# 13-_EtherCAT.net
KiCad netlist of a schematic drawn in Altium Designer
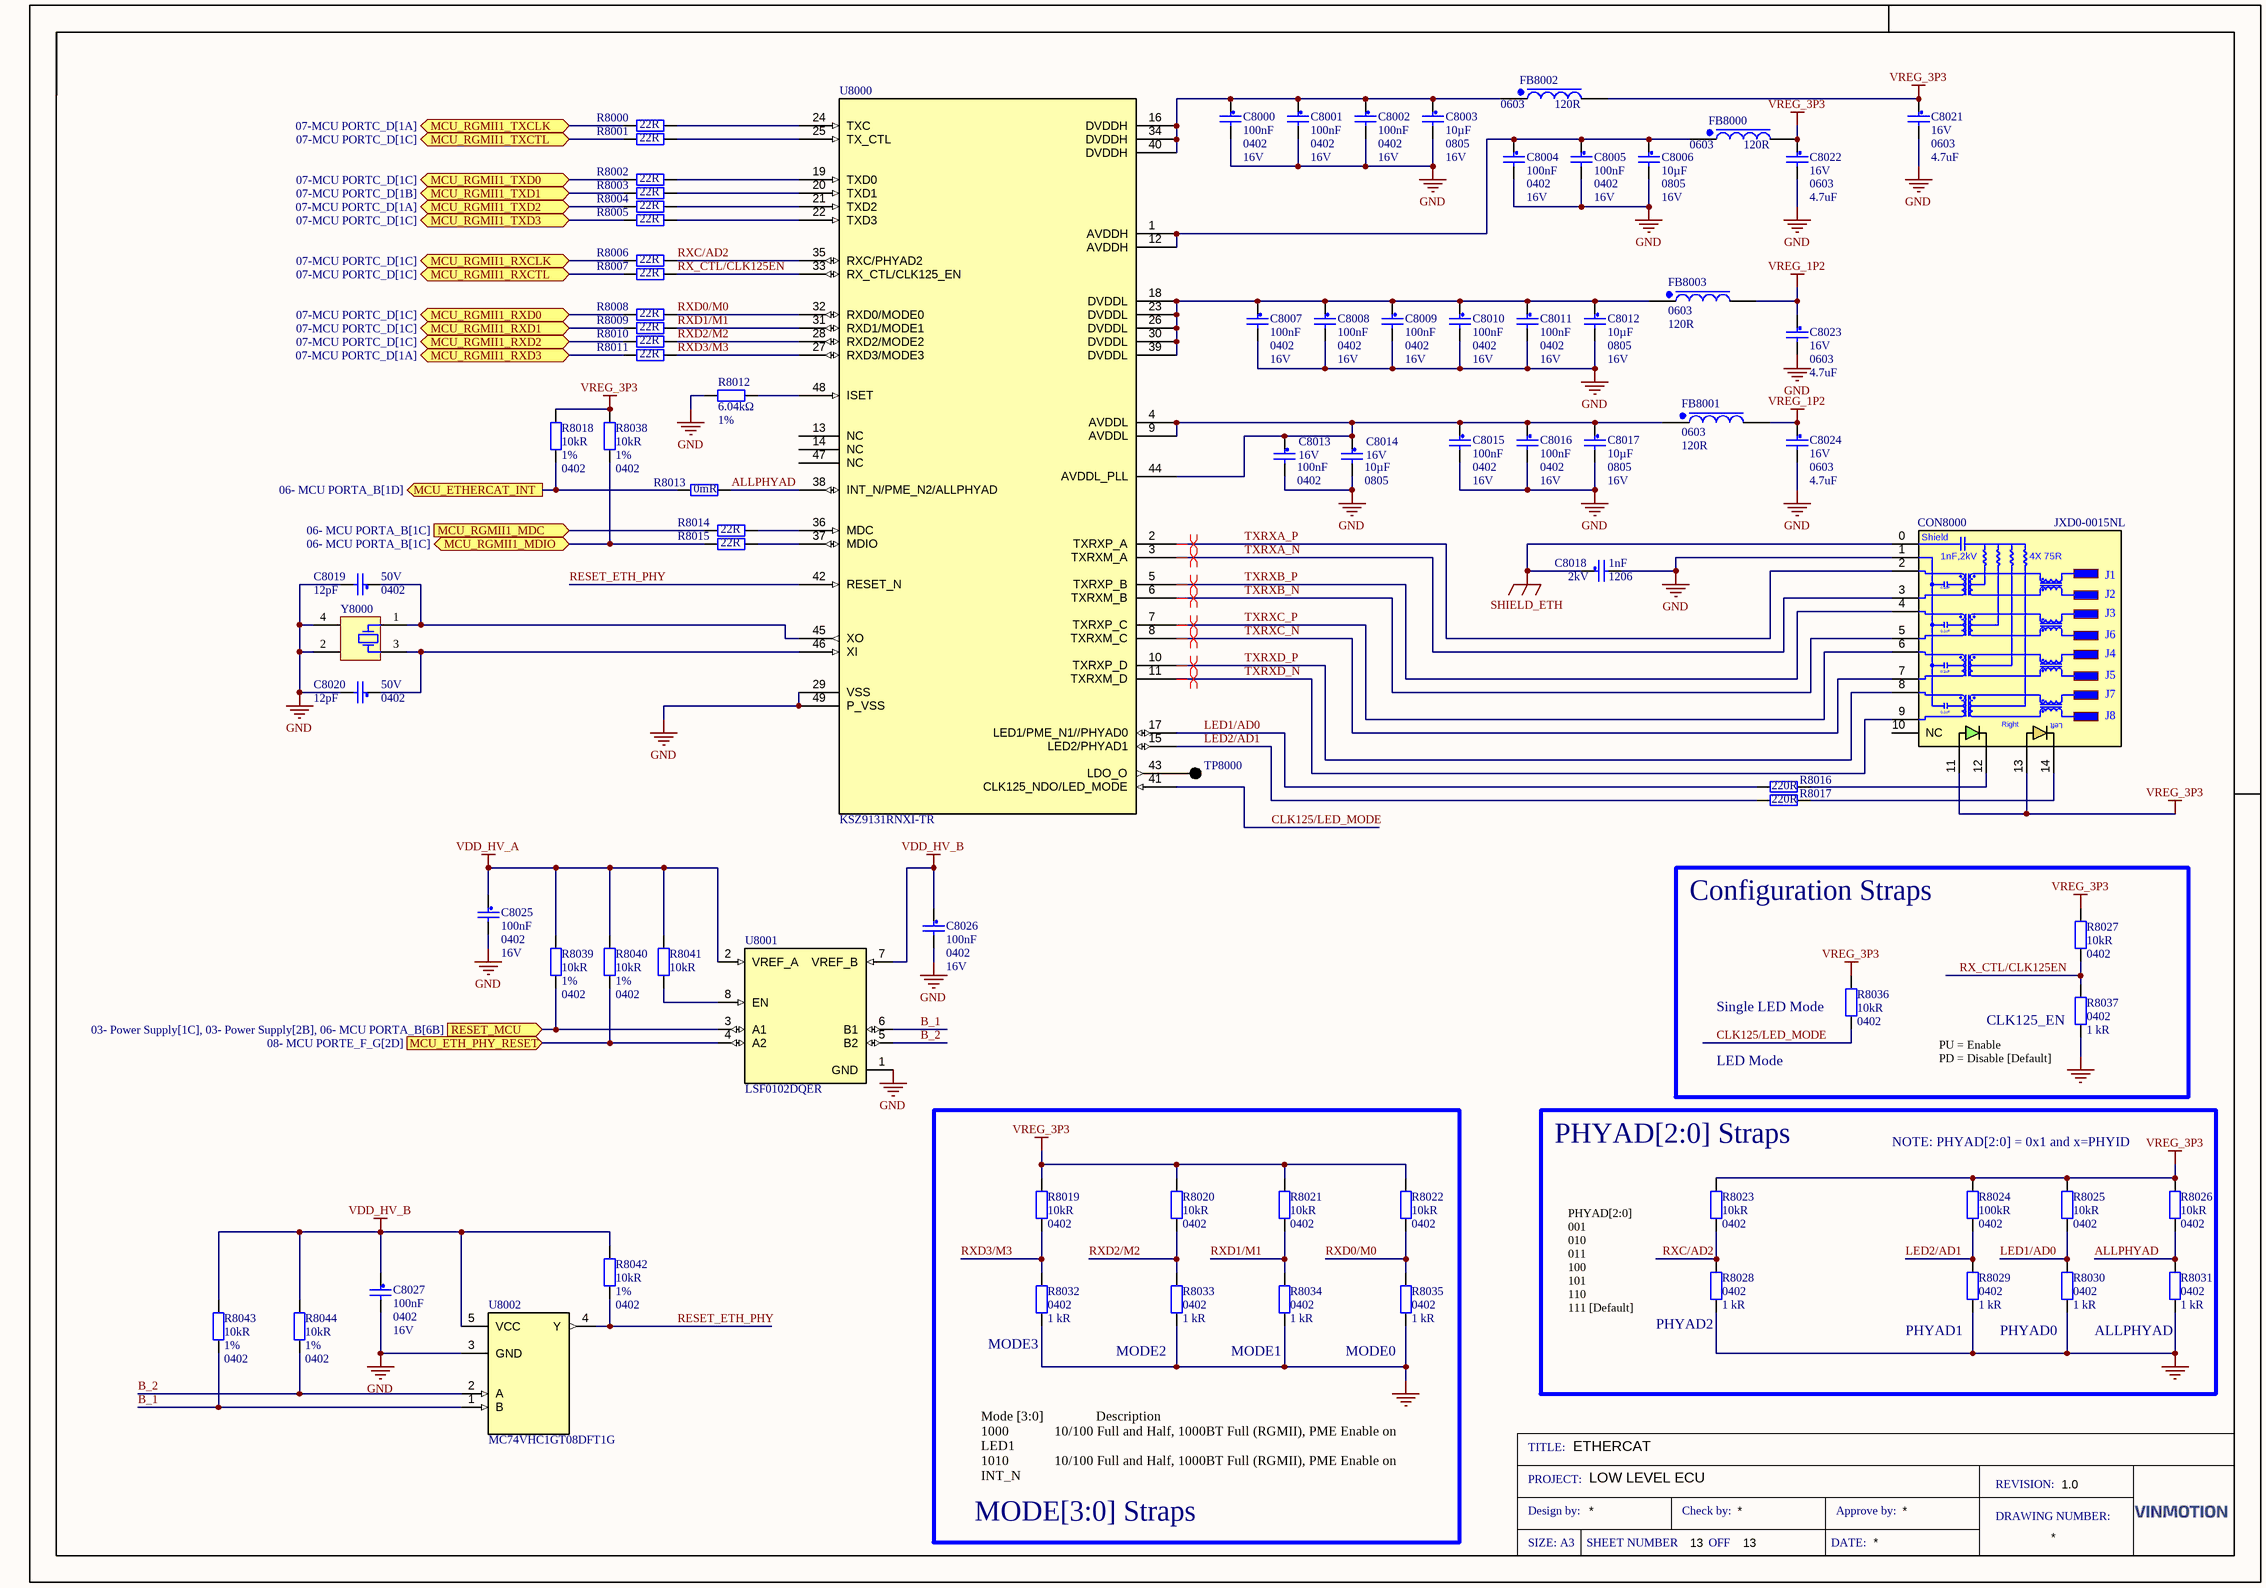
[diagram p0: 13- EtherCAT.SchDoc]

(export (version "E")
  (design (tool "Eeschema 10.0.6"))
  (components
    (comp (ref "C8000")
      (value "0402YC104KAT2A")
      (footprint "CAP0402")
      (description "CAP CER 0.1UF 16V X7R 0402")
      (fields
        (field (name "CAPACITANCE") "100nF")
        (field (name "CASE/PACKAGE") "0402")
        (field (name "VOLTAGE RATING (DC)") "16V")
      )
      (libsource (lib "VMO_Lib") (part "CMP-00988-1"))
    )
    (comp (ref "C8001")
      (value "0402YC104KAT2A")
      (footprint "CAP0402")
      (description "CAP CER 0.1UF 16V X7R 0402")
      (fields
        (field (name "CAPACITANCE") "100nF")
        (field (name "CASE/PACKAGE") "0402")
        (field (name "VOLTAGE RATING (DC)") "16V")
      )
      (libsource (lib "VMO_Lib") (part "CMP-00988-1"))
    )
    (comp (ref "C8002")
      (value "0402YC104KAT2A")
      (footprint "CAP0402")
      (description "CAP CER 0.1UF 16V X7R 0402")
      (fields
        (field (name "CAPACITANCE") "100nF")
        (field (name "CASE/PACKAGE") "0402")
        (field (name "VOLTAGE RATING (DC)") "16V")
      )
      (libsource (lib "VMO_Lib") (part "CMP-00988-1"))
    )
    (comp (ref "C8003")
      (value "10µF")
      (footprint "CAP0805")
      (description "CAP CER 10UF 16V X7R 0805")
      (fields
        (field (name "CASE/PACKAGE") "0805")
        (field (name "MANUFACTURER") "Murata")
        (field (name "MANUFACTURER PART NUMBER") "GRM21BZ71C106KE15L")
        (field (name "VOLTAGE RATING") "16V")
      )
      (libsource (lib "VMO_Lib") (part "CMP-01170-1"))
    )
    (comp (ref "C8004")
      (value "0402YC104KAT2A")
      (footprint "CAP0402")
      (description "CAP CER 0.1UF 16V X7R 0402")
      (fields
        (field (name "CAPACITANCE") "100nF")
        (field (name "CASE/PACKAGE") "0402")
        (field (name "VOLTAGE RATING (DC)") "16V")
      )
      (libsource (lib "VMO_Lib") (part "CMP-00988-1"))
    )
    (comp (ref "C8005")
      (value "0402YC104KAT2A")
      (footprint "CAP0402")
      (description "CAP CER 0.1UF 16V X7R 0402")
      (fields
        (field (name "CAPACITANCE") "100nF")
        (field (name "CASE/PACKAGE") "0402")
        (field (name "VOLTAGE RATING (DC)") "16V")
      )
      (libsource (lib "VMO_Lib") (part "CMP-00988-1"))
    )
    (comp (ref "C8006")
      (value "10µF")
      (footprint "CAP0805")
      (description "CAP CER 10UF 16V X7R 0805")
      (fields
        (field (name "CASE/PACKAGE") "0805")
        (field (name "MANUFACTURER") "Murata")
        (field (name "MANUFACTURER PART NUMBER") "GRM21BZ71C106KE15L")
        (field (name "VOLTAGE RATING") "16V")
      )
      (libsource (lib "VMO_Lib") (part "CMP-01170-1"))
    )
    (comp (ref "C8007")
      (value "0402YC104KAT2A")
      (footprint "CAP0402")
      (description "CAP CER 0.1UF 16V X7R 0402")
      (fields
        (field (name "CAPACITANCE") "100nF")
        (field (name "CASE/PACKAGE") "0402")
        (field (name "VOLTAGE RATING (DC)") "16V")
      )
      (libsource (lib "VMO_Lib") (part "CMP-00988-1"))
    )
    (comp (ref "C8008")
      (value "0402YC104KAT2A")
      (footprint "CAP0402")
      (description "CAP CER 0.1UF 16V X7R 0402")
      (fields
        (field (name "CAPACITANCE") "100nF")
        (field (name "CASE/PACKAGE") "0402")
        (field (name "VOLTAGE RATING (DC)") "16V")
      )
      (libsource (lib "VMO_Lib") (part "CMP-00988-1"))
    )
    (comp (ref "C8009")
      (value "0402YC104KAT2A")
      (footprint "CAP0402")
      (description "CAP CER 0.1UF 16V X7R 0402")
      (fields
        (field (name "CAPACITANCE") "100nF")
        (field (name "CASE/PACKAGE") "0402")
        (field (name "VOLTAGE RATING (DC)") "16V")
      )
      (libsource (lib "VMO_Lib") (part "CMP-00988-1"))
    )
    (comp (ref "C8010")
      (value "0402YC104KAT2A")
      (footprint "CAP0402")
      (description "CAP CER 0.1UF 16V X7R 0402")
      (fields
        (field (name "CAPACITANCE") "100nF")
        (field (name "CASE/PACKAGE") "0402")
        (field (name "VOLTAGE RATING (DC)") "16V")
      )
      (libsource (lib "VMO_Lib") (part "CMP-00988-1"))
    )
    (comp (ref "C8011")
      (value "0402YC104KAT2A")
      (footprint "CAP0402")
      (description "CAP CER 0.1UF 16V X7R 0402")
      (fields
        (field (name "CAPACITANCE") "100nF")
        (field (name "CASE/PACKAGE") "0402")
        (field (name "VOLTAGE RATING (DC)") "16V")
      )
      (libsource (lib "VMO_Lib") (part "CMP-00988-1"))
    )
    (comp (ref "C8012")
      (value "10µF")
      (footprint "CAP0805")
      (description "CAP CER 10UF 16V X7R 0805")
      (fields
        (field (name "CASE/PACKAGE") "0805")
        (field (name "MANUFACTURER") "Murata")
        (field (name "MANUFACTURER PART NUMBER") "GRM21BZ71C106KE15L")
        (field (name "VOLTAGE RATING") "16V")
      )
      (libsource (lib "VMO_Lib") (part "CMP-01170-1"))
    )
    (comp (ref "C8013")
      (value "0402YC104KAT2A")
      (footprint "CAP0402")
      (description "CAP CER 0.1UF 16V X7R 0402")
      (fields
        (field (name "CAPACITANCE") "100nF")
        (field (name "CASE/PACKAGE") "0402")
        (field (name "VOLTAGE RATING (DC)") "16V")
      )
      (libsource (lib "VMO_Lib") (part "CMP-00988-1"))
    )
    (comp (ref "C8014")
      (value "10µF")
      (footprint "CAP0805")
      (description "CAP CER 10UF 16V X7R 0805")
      (fields
        (field (name "CASE/PACKAGE") "0805")
        (field (name "MANUFACTURER") "Murata")
        (field (name "MANUFACTURER PART NUMBER") "GRM21BZ71C106KE15L")
        (field (name "VOLTAGE RATING") "16V")
      )
      (libsource (lib "VMO_Lib") (part "CMP-01170-1"))
    )
    (comp (ref "C8015")
      (value "0402YC104KAT2A")
      (footprint "CAP0402")
      (description "CAP CER 0.1UF 16V X7R 0402")
      (fields
        (field (name "CAPACITANCE") "100nF")
        (field (name "CASE/PACKAGE") "0402")
        (field (name "VOLTAGE RATING (DC)") "16V")
      )
      (libsource (lib "VMO_Lib") (part "CMP-00988-1"))
    )
    (comp (ref "C8016")
      (value "0402YC104KAT2A")
      (footprint "CAP0402")
      (description "CAP CER 0.1UF 16V X7R 0402")
      (fields
        (field (name "CAPACITANCE") "100nF")
        (field (name "CASE/PACKAGE") "0402")
        (field (name "VOLTAGE RATING (DC)") "16V")
      )
      (libsource (lib "VMO_Lib") (part "CMP-00988-1"))
    )
    (comp (ref "C8017")
      (value "10µF")
      (footprint "CAP0805")
      (description "CAP CER 10UF 16V X7R 0805")
      (fields
        (field (name "CASE/PACKAGE") "0805")
        (field (name "MANUFACTURER") "Murata")
        (field (name "MANUFACTURER PART NUMBER") "GRM21BZ71C106KE15L")
        (field (name "VOLTAGE RATING") "16V")
      )
      (libsource (lib "VMO_Lib") (part "CMP-01170-1"))
    )
    (comp (ref "C8018")
      (value "C1206C102KGRACAUTO")
      (footprint "CAP1206")
      (description "CAP CER 1000PF 2KV X7R 1206")
      (fields
        (field (name "TOLERANCE") "10%")
        (field (name "VOLTAGE RATING") "2kV")
        (field (name "CASE/PACKAGE") "1206")
        (field (name "CAPACITANCE") "1nF")
      )
      (libsource (lib "VMO_Lib") (part "CMP-00118-3"))
    )
    (comp (ref "C8019")
      (value "GCM1555C1H120JA16D")
      (footprint "CAP0402")
      (description "CAP CER 12PF 50V C0G/NP0 0402")
      (fields
        (field (name "TOLERANCE") "5%")
        (field (name "VOLTAGE RATING") "50V")
        (field (name "CASE/PACKAGE") "0402")
        (field (name "CAPACITANCE") "12pF")
      )
      (libsource (lib "VMO_Lib") (part "CMP-00203-1"))
    )
    (comp (ref "C8020")
      (value "GCM1555C1H120JA16D")
      (footprint "CAP0402")
      (description "CAP CER 12PF 50V C0G/NP0 0402")
      (fields
        (field (name "TOLERANCE") "5%")
        (field (name "VOLTAGE RATING") "50V")
        (field (name "CASE/PACKAGE") "0402")
        (field (name "CAPACITANCE") "12pF")
      )
      (libsource (lib "VMO_Lib") (part "CMP-00203-1"))
    )
    (comp (ref "C8021")
      (value "GRT188C81C475KE13D")
      (footprint "CAP0603")
      (description "CAP CER 4.7uF 16V 10% X6S 0603 SMD")
      (fields
        (field (name "TOLERANCE") "10%")
        (field (name "VOLTAGE RATING") "16V")
        (field (name "CASE/PACKAGE") "0603")
        (field (name "CAPACITANCE") "4.7uF")
      )
      (libsource (lib "VMO_Lib") (part "CMP-00351-2"))
    )
    (comp (ref "C8022")
      (value "GRT188C81C475KE13D")
      (footprint "CAP0603")
      (description "CAP CER 4.7uF 16V 10% X6S 0603 SMD")
      (fields
        (field (name "TOLERANCE") "10%")
        (field (name "VOLTAGE RATING") "16V")
        (field (name "CASE/PACKAGE") "0603")
        (field (name "CAPACITANCE") "4.7uF")
      )
      (libsource (lib "VMO_Lib") (part "CMP-00351-2"))
    )
    (comp (ref "C8023")
      (value "GRT188C81C475KE13D")
      (footprint "CAP0603")
      (description "CAP CER 4.7uF 16V 10% X6S 0603 SMD")
      (fields
        (field (name "TOLERANCE") "10%")
        (field (name "VOLTAGE RATING") "16V")
        (field (name "CASE/PACKAGE") "0603")
        (field (name "CAPACITANCE") "4.7uF")
      )
      (libsource (lib "VMO_Lib") (part "CMP-00351-2"))
    )
    (comp (ref "C8024")
      (value "GRT188C81C475KE13D")
      (footprint "CAP0603")
      (description "CAP CER 4.7uF 16V 10% X6S 0603 SMD")
      (fields
        (field (name "TOLERANCE") "10%")
        (field (name "VOLTAGE RATING") "16V")
        (field (name "CASE/PACKAGE") "0603")
        (field (name "CAPACITANCE") "4.7uF")
      )
      (libsource (lib "VMO_Lib") (part "CMP-00351-2"))
    )
    (comp (ref "C8025")
      (value "0402YC104KAT2A")
      (footprint "CAP0402")
      (description "CAP CER 0.1UF 16V X7R 0402")
      (fields
        (field (name "CAPACITANCE") "100nF")
        (field (name "CASE/PACKAGE") "0402")
        (field (name "VOLTAGE RATING (DC)") "16V")
      )
      (libsource (lib "VMO_Lib") (part "CMP-00988-1"))
    )
    (comp (ref "C8026")
      (value "0402YC104KAT2A")
      (footprint "CAP0402")
      (description "CAP CER 0.1UF 16V X7R 0402")
      (fields
        (field (name "CAPACITANCE") "100nF")
        (field (name "CASE/PACKAGE") "0402")
        (field (name "VOLTAGE RATING (DC)") "16V")
      )
      (libsource (lib "VMO_Lib") (part "CMP-00988-1"))
    )
    (comp (ref "C8027")
      (value "0402YC104KAT2A")
      (footprint "CAP0402")
      (description "CAP CER 0.1UF 16V X7R 0402")
      (fields
        (field (name "CAPACITANCE") "100nF")
        (field (name "CASE/PACKAGE") "0402")
        (field (name "VOLTAGE RATING (DC)") "16V")
      )
      (libsource (lib "VMO_Lib") (part "CMP-00988-1"))
    )
    (comp (ref "CON8000")
      (value "JXD0-0015NL")
      (footprint "RJ45")
      (description "1 Port RJ45 Through Hole 10/100/1000 Base-T, AutoMDIX")
      (fields (field (name "MANUFACTURER") "Pulse Electronics"))
      (libsource (lib "VMO_Lib") (part "CMP-01191-1"))
    )
    (comp (ref "FB8000")
      (value "BLM18KG121TH1D")
      (footprint "FB0603")
      (description "FERRITE BEAD 120 OHM 0603 1LN")
      (fields (field (name "CASE/PACKAGE") "0603") (field (name "IMPEDANCE") "120R"))
      (libsource (lib "VMO_Lib") (part "CMP-ROOT-0013-6"))
    )
    (comp (ref "FB8001")
      (value "BLM18KG121TH1D")
      (footprint "FB0603")
      (description "FERRITE BEAD 120 OHM 0603 1LN")
      (fields (field (name "CASE/PACKAGE") "0603") (field (name "IMPEDANCE") "120R"))
      (libsource (lib "VMO_Lib") (part "CMP-ROOT-0013-6"))
    )
    (comp (ref "FB8002")
      (value "BLM18KG121TH1D")
      (footprint "FB0603")
      (description "FERRITE BEAD 120 OHM 0603 1LN")
      (fields (field (name "CASE/PACKAGE") "0603") (field (name "IMPEDANCE") "120R"))
      (libsource (lib "VMO_Lib") (part "CMP-ROOT-0013-6"))
    )
    (comp (ref "FB8003")
      (value "BLM18KG121TH1D")
      (footprint "FB0603")
      (description "FERRITE BEAD 120 OHM 0603 1LN")
      (fields (field (name "CASE/PACKAGE") "0603") (field (name "IMPEDANCE") "120R"))
      (libsource (lib "VMO_Lib") (part "CMP-ROOT-0013-6"))
    )
    (comp (ref "R8000")
      (value "CRCW040222R0JNED")
      (footprint "RES0402")
      (description "RES SMD 22 OHM 5% 1/16W 0402")
      (fields (field (name "TOLERANCE") "5%") (field (name "RESISTANCE") "22R"))
      (libsource (lib "VMO_Lib") (part "CMP-00237-1"))
    )
    (comp (ref "R8001")
      (value "CRCW040222R0JNED")
      (footprint "RES0402")
      (description "RES SMD 22 OHM 5% 1/16W 0402")
      (fields (field (name "TOLERANCE") "5%") (field (name "RESISTANCE") "22R"))
      (libsource (lib "VMO_Lib") (part "CMP-00237-1"))
    )
    (comp (ref "R8002")
      (value "CRCW040222R0JNED")
      (footprint "RES0402")
      (description "RES SMD 22 OHM 5% 1/16W 0402")
      (fields (field (name "TOLERANCE") "5%") (field (name "RESISTANCE") "22R"))
      (libsource (lib "VMO_Lib") (part "CMP-00237-1"))
    )
    (comp (ref "R8003")
      (value "CRCW040222R0JNED")
      (footprint "RES0402")
      (description "RES SMD 22 OHM 5% 1/16W 0402")
      (fields (field (name "TOLERANCE") "5%") (field (name "RESISTANCE") "22R"))
      (libsource (lib "VMO_Lib") (part "CMP-00237-1"))
    )
    (comp (ref "R8004")
      (value "CRCW040222R0JNED")
      (footprint "RES0402")
      (description "RES SMD 22 OHM 5% 1/16W 0402")
      (fields (field (name "TOLERANCE") "5%") (field (name "RESISTANCE") "22R"))
      (libsource (lib "VMO_Lib") (part "CMP-00237-1"))
    )
    (comp (ref "R8005")
      (value "CRCW040222R0JNED")
      (footprint "RES0402")
      (description "RES SMD 22 OHM 5% 1/16W 0402")
      (fields (field (name "TOLERANCE") "5%") (field (name "RESISTANCE") "22R"))
      (libsource (lib "VMO_Lib") (part "CMP-00237-1"))
    )
    (comp (ref "R8006")
      (value "CRCW040222R0JNED")
      (footprint "RES0402")
      (description "RES SMD 22 OHM 5% 1/16W 0402")
      (fields (field (name "TOLERANCE") "5%") (field (name "RESISTANCE") "22R"))
      (libsource (lib "VMO_Lib") (part "CMP-00237-1"))
    )
    (comp (ref "R8007")
      (value "CRCW040222R0JNED")
      (footprint "RES0402")
      (description "RES SMD 22 OHM 5% 1/16W 0402")
      (fields (field (name "TOLERANCE") "5%") (field (name "RESISTANCE") "22R"))
      (libsource (lib "VMO_Lib") (part "CMP-00237-1"))
    )
    (comp (ref "R8008")
      (value "CRCW040222R0JNED")
      (footprint "RES0402")
      (description "RES SMD 22 OHM 5% 1/16W 0402")
      (fields (field (name "TOLERANCE") "5%") (field (name "RESISTANCE") "22R"))
      (libsource (lib "VMO_Lib") (part "CMP-00237-1"))
    )
    (comp (ref "R8009")
      (value "CRCW040222R0JNED")
      (footprint "RES0402")
      (description "RES SMD 22 OHM 5% 1/16W 0402")
      (fields (field (name "TOLERANCE") "5%") (field (name "RESISTANCE") "22R"))
      (libsource (lib "VMO_Lib") (part "CMP-00237-1"))
    )
    (comp (ref "R8010")
      (value "CRCW040222R0JNED")
      (footprint "RES0402")
      (description "RES SMD 22 OHM 5% 1/16W 0402")
      (fields (field (name "TOLERANCE") "5%") (field (name "RESISTANCE") "22R"))
      (libsource (lib "VMO_Lib") (part "CMP-00237-1"))
    )
    (comp (ref "R8011")
      (value "CRCW040222R0JNED")
      (footprint "RES0402")
      (description "RES SMD 22 OHM 5% 1/16W 0402")
      (fields (field (name "TOLERANCE") "5%") (field (name "RESISTANCE") "22R"))
      (libsource (lib "VMO_Lib") (part "CMP-00237-1"))
    )
    (comp (ref "R8012")
      (value "6.04kΩ")
      (footprint "RES0402")
      (description "RES 6.04K OHM 1% 1/16W 0402")
      (fields
        (field (name "MANUFACTURER") "Vishay")
        (field (name "MANUFACTURER PART NUMBER") "CRCW04026K04FKEDC")
        (field (name "TOLERANCE") "1%")
      )
      (libsource (lib "VMO_Lib") (part "CMP-01177-1"))
    )
    (comp (ref "R8013")
      (value "RMCF0402ZT0R00")
      (footprint "RES0402")
      (description "RES 0R 1/16W 1% 0402 SMD")
      (fields (field (name "RESISTANCE") "0mR"))
      (libsource (lib "VMO_Lib") (part "CMP-ROOT-0037-10"))
    )
    (comp (ref "R8014")
      (value "CRCW040222R0JNED")
      (footprint "RES0402")
      (description "RES SMD 22 OHM 5% 1/16W 0402")
      (fields (field (name "TOLERANCE") "5%") (field (name "RESISTANCE") "22R"))
      (libsource (lib "VMO_Lib") (part "CMP-00237-1"))
    )
    (comp (ref "R8015")
      (value "CRCW040222R0JNED")
      (footprint "RES0402")
      (description "RES SMD 22 OHM 5% 1/16W 0402")
      (fields (field (name "TOLERANCE") "5%") (field (name "RESISTANCE") "22R"))
      (libsource (lib "VMO_Lib") (part "CMP-00237-1"))
    )
    (comp (ref "R8016")
      (value "220R")
      (footprint "RES0402")
      (description "RES SMD 220 OHM 1% 1/10W 0402")
      (fields
        (field (name "MANUFACTURER") "Vishay")
        (field (name "MANUFACTURER PART NUMBER") "CRCW0402220RFKED")
      )
      (libsource (lib "VMO_Lib") (part "CMP-01126-1"))
    )
    (comp (ref "R8017")
      (value "220R")
      (footprint "RES0402")
      (description "RES SMD 220 OHM 1% 1/10W 0402")
      (fields
        (field (name "MANUFACTURER") "Vishay")
        (field (name "MANUFACTURER PART NUMBER") "CRCW0402220RFKED")
      )
      (libsource (lib "VMO_Lib") (part "CMP-01126-1"))
    )
    (comp (ref "R8018")
      (value "10kR")
      (footprint "RES0402")
      (description "RES 10K OHM 1% 1/16W 0402")
      (fields
        (field (name "MANUFACTURER") "Stackpole Electronics")
        (field (name "MANUFACTURER PART NUMBER") "RMCF0402FT10K0")
        (field (name "TOLERANCE") "1%")
        (field (name "CASE/PACKAGE") "0402")
      )
      (libsource (lib "VMO_Lib") (part "CMP-01105-1"))
    )
    (comp (ref "R8019")
      (value "ERJ2GEJ103X")
      (footprint "RES0402")
      (description "RES SMD 10K OHM 5% 1/10W 0402")
      (fields
        (field (name "TOLERANCE") "5%")
        (field (name "RESISTANCE") "10kR")
        (field (name "CASE/PACKAGE") "0402")
      )
      (libsource (lib "VMO_Lib") (part "CMP-00039-6"))
    )
    (comp (ref "R8020")
      (value "ERJ2GEJ103X")
      (footprint "RES0402")
      (description "RES SMD 10K OHM 5% 1/10W 0402")
      (fields
        (field (name "TOLERANCE") "5%")
        (field (name "RESISTANCE") "10kR")
        (field (name "CASE/PACKAGE") "0402")
      )
      (libsource (lib "VMO_Lib") (part "CMP-00039-6"))
    )
    (comp (ref "R8021")
      (value "ERJ2GEJ103X")
      (footprint "RES0402")
      (description "RES SMD 10K OHM 5% 1/10W 0402")
      (fields
        (field (name "TOLERANCE") "5%")
        (field (name "RESISTANCE") "10kR")
        (field (name "CASE/PACKAGE") "0402")
      )
      (libsource (lib "VMO_Lib") (part "CMP-00039-6"))
    )
    (comp (ref "R8022")
      (value "ERJ2GEJ103X")
      (footprint "RES0402")
      (description "RES SMD 10K OHM 5% 1/10W 0402")
      (fields
        (field (name "TOLERANCE") "5%")
        (field (name "RESISTANCE") "10kR")
        (field (name "CASE/PACKAGE") "0402")
      )
      (libsource (lib "VMO_Lib") (part "CMP-00039-6"))
    )
    (comp (ref "R8023")
      (value "ERJ2GEJ103X")
      (footprint "RES0402")
      (description "RES SMD 10K OHM 5% 1/10W 0402")
      (fields
        (field (name "TOLERANCE") "5%")
        (field (name "RESISTANCE") "10kR")
        (field (name "CASE/PACKAGE") "0402")
      )
      (libsource (lib "VMO_Lib") (part "CMP-00039-6"))
    )
    (comp (ref "R8024")
      (value "RMCF0402FT100K")
      (footprint "RES0402")
      (description "RES 100kR 1/16W 1% 0402 SMD")
      (fields
        (field (name "TOLERANCE") "1%")
        (field (name "RESISTANCE") "100kR")
        (field (name "CASE/PACKAGE") "0402")
      )
      (libsource (lib "VMO_Lib") (part "CMP-00623-2"))
    )
    (comp (ref "R8025")
      (value "ERJ2GEJ103X")
      (footprint "RES0402")
      (description "RES SMD 10K OHM 5% 1/10W 0402")
      (fields
        (field (name "TOLERANCE") "5%")
        (field (name "RESISTANCE") "10kR")
        (field (name "CASE/PACKAGE") "0402")
      )
      (libsource (lib "VMO_Lib") (part "CMP-00039-6"))
    )
    (comp (ref "R8026")
      (value "ERJ2GEJ103X")
      (footprint "RES0402")
      (description "RES SMD 10K OHM 5% 1/10W 0402")
      (fields
        (field (name "TOLERANCE") "5%")
        (field (name "RESISTANCE") "10kR")
        (field (name "CASE/PACKAGE") "0402")
      )
      (libsource (lib "VMO_Lib") (part "CMP-00039-6"))
    )
    (comp (ref "R8027")
      (value "ERJ2GEJ103X")
      (footprint "RES0402")
      (description "RES SMD 10K OHM 5% 1/10W 0402")
      (fields
        (field (name "TOLERANCE") "5%")
        (field (name "RESISTANCE") "10kR")
        (field (name "CASE/PACKAGE") "0402")
      )
      (libsource (lib "VMO_Lib") (part "CMP-00039-6"))
    )
    (comp (ref "R8028")
      (value "RK73H1ETTP1001F")
      (footprint "RES0402")
      (description "RES 1K OHM 1% 1/10W 0402")
      (fields
        (field (name "TOLERANCE") "1%")
        (field (name "CASE/PACKAGE") "0402")
        (field (name "RESISTANCE") "1 kR")
      )
      (libsource (lib "VMO_Lib") (part "CMP-00903-1"))
    )
    (comp (ref "R8029")
      (value "RK73H1ETTP1001F")
      (footprint "RES0402")
      (description "RES 1K OHM 1% 1/10W 0402")
      (fields
        (field (name "TOLERANCE") "1%")
        (field (name "CASE/PACKAGE") "0402")
        (field (name "RESISTANCE") "1 kR")
      )
      (libsource (lib "VMO_Lib") (part "CMP-00903-1"))
    )
    (comp (ref "R8030")
      (value "RK73H1ETTP1001F")
      (footprint "RES0402")
      (description "RES 1K OHM 1% 1/10W 0402")
      (fields
        (field (name "TOLERANCE") "1%")
        (field (name "CASE/PACKAGE") "0402")
        (field (name "RESISTANCE") "1 kR")
      )
      (libsource (lib "VMO_Lib") (part "CMP-00903-1"))
    )
    (comp (ref "R8031")
      (value "RK73H1ETTP1001F")
      (footprint "RES0402")
      (description "RES 1K OHM 1% 1/10W 0402")
      (fields
        (field (name "TOLERANCE") "1%")
        (field (name "CASE/PACKAGE") "0402")
        (field (name "RESISTANCE") "1 kR")
      )
      (libsource (lib "VMO_Lib") (part "CMP-00903-1"))
    )
    (comp (ref "R8032")
      (value "RK73H1ETTP1001F")
      (footprint "RES0402")
      (description "RES 1K OHM 1% 1/10W 0402")
      (fields
        (field (name "TOLERANCE") "1%")
        (field (name "CASE/PACKAGE") "0402")
        (field (name "RESISTANCE") "1 kR")
      )
      (libsource (lib "VMO_Lib") (part "CMP-00903-1"))
    )
    (comp (ref "R8033")
      (value "RK73H1ETTP1001F")
      (footprint "RES0402")
      (description "RES 1K OHM 1% 1/10W 0402")
      (fields
        (field (name "TOLERANCE") "1%")
        (field (name "CASE/PACKAGE") "0402")
        (field (name "RESISTANCE") "1 kR")
      )
      (libsource (lib "VMO_Lib") (part "CMP-00903-1"))
    )
    (comp (ref "R8034")
      (value "RK73H1ETTP1001F")
      (footprint "RES0402")
      (description "RES 1K OHM 1% 1/10W 0402")
      (fields
        (field (name "TOLERANCE") "1%")
        (field (name "CASE/PACKAGE") "0402")
        (field (name "RESISTANCE") "1 kR")
      )
      (libsource (lib "VMO_Lib") (part "CMP-00903-1"))
    )
    (comp (ref "R8035")
      (value "RK73H1ETTP1001F")
      (footprint "RES0402")
      (description "RES 1K OHM 1% 1/10W 0402")
      (fields
        (field (name "TOLERANCE") "1%")
        (field (name "CASE/PACKAGE") "0402")
        (field (name "RESISTANCE") "1 kR")
      )
      (libsource (lib "VMO_Lib") (part "CMP-00903-1"))
    )
    (comp (ref "R8036")
      (value "ERJ2GEJ103X")
      (footprint "RES0402")
      (description "RES SMD 10K OHM 5% 1/10W 0402")
      (fields
        (field (name "TOLERANCE") "5%")
        (field (name "RESISTANCE") "10kR")
        (field (name "CASE/PACKAGE") "0402")
      )
      (libsource (lib "VMO_Lib") (part "CMP-00039-6"))
    )
    (comp (ref "R8037")
      (value "RK73H1ETTP1001F")
      (footprint "RES0402")
      (description "RES 1K OHM 1% 1/10W 0402")
      (fields
        (field (name "TOLERANCE") "1%")
        (field (name "CASE/PACKAGE") "0402")
        (field (name "RESISTANCE") "1 kR")
      )
      (libsource (lib "VMO_Lib") (part "CMP-00903-1"))
    )
    (comp (ref "R8038")
      (value "10kR")
      (footprint "RES0402")
      (description "RES 10K OHM 1% 1/16W 0402")
      (fields
        (field (name "MANUFACTURER") "Stackpole Electronics")
        (field (name "MANUFACTURER PART NUMBER") "RMCF0402FT10K0")
        (field (name "TOLERANCE") "1%")
        (field (name "CASE/PACKAGE") "0402")
      )
      (libsource (lib "VMO_Lib") (part "CMP-01105-1"))
    )
    (comp (ref "R8039")
      (value "10kR")
      (footprint "RES0402")
      (description "RES 10K OHM 1% 1/16W 0402")
      (fields
        (field (name "MANUFACTURER") "Stackpole Electronics")
        (field (name "MANUFACTURER PART NUMBER") "RMCF0402FT10K0")
        (field (name "TOLERANCE") "1%")
        (field (name "CASE/PACKAGE") "0402")
      )
      (libsource (lib "VMO_Lib") (part "CMP-01105-1"))
    )
    (comp (ref "R8040")
      (value "10kR")
      (footprint "RES0402")
      (description "RES 10K OHM 1% 1/16W 0402")
      (fields
        (field (name "MANUFACTURER") "Stackpole Electronics")
        (field (name "MANUFACTURER PART NUMBER") "RMCF0402FT10K0")
        (field (name "TOLERANCE") "1%")
        (field (name "CASE/PACKAGE") "0402")
      )
      (libsource (lib "VMO_Lib") (part "CMP-01105-1"))
    )
    (comp (ref "R8041")
      (value "10kR")
      (footprint "RES0402")
      (description "RES 10K OHM 1% 1/16W 0402")
      (fields
        (field (name "MANUFACTURER") "Stackpole Electronics")
        (field (name "MANUFACTURER PART NUMBER") "RMCF0402FT10K0")
      )
      (libsource (lib "VMO_Lib") (part "CMP-01105-1"))
    )
    (comp (ref "R8042")
      (value "10kR")
      (footprint "RES0402")
      (description "RES 10K OHM 1% 1/16W 0402")
      (fields
        (field (name "MANUFACTURER") "Stackpole Electronics")
        (field (name "MANUFACTURER PART NUMBER") "RMCF0402FT10K0")
        (field (name "TOLERANCE") "1%")
        (field (name "CASE/PACKAGE") "0402")
      )
      (libsource (lib "VMO_Lib") (part "CMP-01105-1"))
    )
    (comp (ref "R8043")
      (value "10kR")
      (footprint "RES0402")
      (description "RES 10K OHM 1% 1/16W 0402")
      (fields
        (field (name "MANUFACTURER") "Stackpole Electronics")
        (field (name "MANUFACTURER PART NUMBER") "RMCF0402FT10K0")
        (field (name "TOLERANCE") "1%")
        (field (name "CASE/PACKAGE") "0402")
      )
      (libsource (lib "VMO_Lib") (part "CMP-01105-1"))
    )
    (comp (ref "R8044")
      (value "10kR")
      (footprint "RES0402")
      (description "RES 10K OHM 1% 1/16W 0402")
      (fields
        (field (name "MANUFACTURER") "Stackpole Electronics")
        (field (name "MANUFACTURER PART NUMBER") "RMCF0402FT10K0")
        (field (name "TOLERANCE") "1%")
        (field (name "CASE/PACKAGE") "0402")
      )
      (libsource (lib "VMO_Lib") (part "CMP-01105-1"))
    )
    (comp (ref "TP8000")
      (value "TP")
      (footprint "TP-SMD-R1")
      (description "Test Point 1x1mm")
      (libsource (lib "VMO_Lib") (part "CMP-ROOT-0080-12"))
    )
    (comp (ref "U8000")
      (value "KSZ9131RNXI-TR")
      (footprint "QFN50P700X700X90_HS-49N")
      (description "IC TXRX FULL/HALF 4/4 48QFN")
      (fields (field (name "MANUFACTURER") "Microchip"))
      (libsource (lib "VMO_Lib") (part "CMP-01190-1"))
    )
    (comp (ref "U8001")
      (value "LSF0102DQER")
      (footprint "8-XFDFN")
      (description "IC VOLTAGE LEVEL BIDIR 8-X2SON")
      (fields (field (name "MANUFACTURER") "Texas Instruments"))
      (libsource (lib "VMO_Lib") (part "CMP-01193-1"))
    )
    (comp (ref "U8002")
      (value "MC74VHC1GT08DFT1G")
      (footprint "SOT95P280X145-5N")
      (description "IC GATE AND 1CH 2-INP SC88A")
      (fields (field (name "MANUFACTURER") "onsemi"))
      (libsource (lib "VMO_Lib") (part "CMP-01194-1"))
    )
    (comp (ref "Y8000")
      (value "NX3225SA-25.000M-STD-CRS-2")
      (footprint "NDK_NX3225SA-25.000M-STD-CRS-2_R")
      (description "CRYSTAL 25.0000MHZ 8PF SMD")
      (libsource (lib "VMO_Lib") (part "CMP-00003-5"))
    )
  )
  (nets
    (net (code "1") (name "/ALLPHYAD") (class "Default")
      (node (ref "R8013") (pin "2") (pinfunction "2_2") (pintype "passive"))
      (node (ref "R8026") (pin "1") (pinfunction "1_1") (pintype "passive"))
      (node (ref "R8031") (pin "2") (pinfunction "2_2") (pintype "passive"))
      (node (ref "U8000") (pin "38") (pinfunction "INT_N/PME_N2/ALLPHYAD_38") (pintype "bidirectional"))
    )
    (net (code "2") (name "/B_1") (class "Default")
      (node (ref "R8043") (pin "1") (pinfunction "1_1") (pintype "passive"))
      (node (ref "U8001") (pin "6") (pinfunction "B1_6") (pintype "bidirectional"))
      (node (ref "U8002") (pin "1") (pinfunction "B_1") (pintype "input"))
    )
    (net (code "3") (name "/B_2") (class "Default")
      (node (ref "R8044") (pin "1") (pinfunction "1_1") (pintype "passive"))
      (node (ref "U8001") (pin "5") (pinfunction "B2_5") (pintype "bidirectional"))
      (node (ref "U8002") (pin "2") (pinfunction "A_2") (pintype "input"))
    )
    (net (code "4") (name "/CLK125{slash}LED_MODE") (class "Default")
      (node (ref "R8036") (pin "1") (pinfunction "1_1") (pintype "passive"))
      (node (ref "U8000") (pin "41") (pinfunction "CLK125_NDO/LED_MODE_41") (pintype "input"))
    )
    (net (code "5") (name "/LED1{slash}AD0") (class "Default")
      (node (ref "R8016") (pin "2") (pinfunction "2_2") (pintype "passive"))
      (node (ref "R8025") (pin "1") (pinfunction "1_1") (pintype "passive"))
      (node (ref "R8030") (pin "2") (pinfunction "2_2") (pintype "passive"))
      (node (ref "U8000") (pin "17") (pinfunction "LED1/PME_N1//PHYAD0_17") (pintype "bidirectional"))
    )
    (net (code "6") (name "/LED2{slash}AD1") (class "Default")
      (node (ref "R8017") (pin "2") (pinfunction "2_2") (pintype "passive"))
      (node (ref "R8024") (pin "1") (pinfunction "1_1") (pintype "passive"))
      (node (ref "R8029") (pin "2") (pinfunction "2_2") (pintype "passive"))
      (node (ref "U8000") (pin "15") (pinfunction "LED2/PHYAD1_15") (pintype "bidirectional"))
    )
    (net (code "7") (name "/MCU_ETHERCAT_INT") (class "Default")
      (node (ref "R8013") (pin "1") (pinfunction "1_1") (pintype "passive"))
      (node (ref "R8018") (pin "1") (pinfunction "1_1") (pintype "passive"))
    )
    (net (code "8") (name "/MCU_ETH_PHY_RESET") (class "Default")
      (node (ref "R8040") (pin "1") (pinfunction "1_1") (pintype "passive"))
      (node (ref "U8001") (pin "4") (pinfunction "A2_4") (pintype "bidirectional"))
    )
    (net (code "9") (name "/MCU_RGMII1_MDC") (class "Default")
      (node (ref "R8014") (pin "1") (pinfunction "1_1") (pintype "passive"))
    )
    (net (code "10") (name "/MCU_RGMII1_MDIO") (class "Default")
      (node (ref "R8015") (pin "1") (pinfunction "1_1") (pintype "passive"))
      (node (ref "R8038") (pin "1") (pinfunction "1_1") (pintype "passive"))
    )
    (net (code "11") (name "/MCU_RGMII1_RXCLK") (class "Default")
      (node (ref "R8006") (pin "1") (pinfunction "1_1") (pintype "passive"))
    )
    (net (code "12") (name "/MCU_RGMII1_RXCTL") (class "Default")
      (node (ref "R8007") (pin "1") (pinfunction "1_1") (pintype "passive"))
    )
    (net (code "13") (name "/MCU_RGMII1_RXD0") (class "Default")
      (node (ref "R8008") (pin "1") (pinfunction "1_1") (pintype "passive"))
    )
    (net (code "14") (name "/MCU_RGMII1_RXD1") (class "Default")
      (node (ref "R8009") (pin "1") (pinfunction "1_1") (pintype "passive"))
    )
    (net (code "15") (name "/MCU_RGMII1_RXD2") (class "Default")
      (node (ref "R8010") (pin "1") (pinfunction "1_1") (pintype "passive"))
    )
    (net (code "16") (name "/MCU_RGMII1_RXD3") (class "Default")
      (node (ref "R8011") (pin "1") (pinfunction "1_1") (pintype "passive"))
    )
    (net (code "17") (name "/MCU_RGMII1_TXCLK") (class "Default")
      (node (ref "R8000") (pin "1") (pinfunction "1_1") (pintype "passive"))
    )
    (net (code "18") (name "/MCU_RGMII1_TXCTL") (class "Default")
      (node (ref "R8001") (pin "1") (pinfunction "1_1") (pintype "passive"))
    )
    (net (code "19") (name "/MCU_RGMII1_TXD0") (class "Default")
      (node (ref "R8002") (pin "1") (pinfunction "1_1") (pintype "passive"))
    )
    (net (code "20") (name "/MCU_RGMII1_TXD1") (class "Default")
      (node (ref "R8003") (pin "1") (pinfunction "1_1") (pintype "passive"))
    )
    (net (code "21") (name "/MCU_RGMII1_TXD2") (class "Default")
      (node (ref "R8004") (pin "1") (pinfunction "1_1") (pintype "passive"))
    )
    (net (code "22") (name "/MCU_RGMII1_TXD3") (class "Default")
      (node (ref "R8005") (pin "1") (pinfunction "1_1") (pintype "passive"))
    )
    (net (code "23") (name "/RESET_ETH_PHY") (class "Default")
      (node (ref "R8042") (pin "1") (pinfunction "1_1") (pintype "passive"))
      (node (ref "U8000") (pin "42") (pinfunction "RESET_N_42") (pintype "input"))
      (node (ref "U8002") (pin "4") (pinfunction "Y_4") (pintype "output"))
    )
    (net (code "24") (name "/RESET_MCU") (class "Default")
      (node (ref "R8039") (pin "1") (pinfunction "1_1") (pintype "passive"))
      (node (ref "U8001") (pin "3") (pinfunction "A1_3") (pintype "bidirectional"))
    )
    (net (code "25") (name "/RXC{slash}AD2") (class "Default")
      (node (ref "R8006") (pin "2") (pinfunction "2_2") (pintype "passive"))
      (node (ref "R8023") (pin "1") (pinfunction "1_1") (pintype "passive"))
      (node (ref "R8028") (pin "2") (pinfunction "2_2") (pintype "passive"))
      (node (ref "U8000") (pin "35") (pinfunction "RXC/PHYAD2_35") (pintype "bidirectional"))
    )
    (net (code "26") (name "/RXD0{slash}M0") (class "Default")
      (node (ref "R8008") (pin "2") (pinfunction "2_2") (pintype "passive"))
      (node (ref "R8022") (pin "1") (pinfunction "1_1") (pintype "passive"))
      (node (ref "R8035") (pin "2") (pinfunction "2_2") (pintype "passive"))
      (node (ref "U8000") (pin "32") (pinfunction "RXD0/MODE0_32") (pintype "bidirectional"))
    )
    (net (code "27") (name "/RXD1{slash}M1") (class "Default")
      (node (ref "R8009") (pin "2") (pinfunction "2_2") (pintype "passive"))
      (node (ref "R8021") (pin "1") (pinfunction "1_1") (pintype "passive"))
      (node (ref "R8034") (pin "2") (pinfunction "2_2") (pintype "passive"))
      (node (ref "U8000") (pin "31") (pinfunction "RXD1/MODE1_31") (pintype "bidirectional"))
    )
    (net (code "28") (name "/RXD2{slash}M2") (class "Default")
      (node (ref "R8010") (pin "2") (pinfunction "2_2") (pintype "passive"))
      (node (ref "R8020") (pin "1") (pinfunction "1_1") (pintype "passive"))
      (node (ref "R8033") (pin "2") (pinfunction "2_2") (pintype "passive"))
      (node (ref "U8000") (pin "28") (pinfunction "RXD2/MODE2_28") (pintype "bidirectional"))
    )
    (net (code "29") (name "/RXD3{slash}M3") (class "Default")
      (node (ref "R8011") (pin "2") (pinfunction "2_2") (pintype "passive"))
      (node (ref "R8019") (pin "1") (pinfunction "1_1") (pintype "passive"))
      (node (ref "R8032") (pin "2") (pinfunction "2_2") (pintype "passive"))
      (node (ref "U8000") (pin "27") (pinfunction "RXD3/MODE3_27") (pintype "bidirectional"))
    )
    (net (code "30") (name "/RX_CTL{slash}CLK125EN") (class "Default")
      (node (ref "R8007") (pin "2") (pinfunction "2_2") (pintype "passive"))
      (node (ref "R8027") (pin "1") (pinfunction "1_1") (pintype "passive"))
      (node (ref "R8037") (pin "2") (pinfunction "2_2") (pintype "passive"))
      (node (ref "U8000") (pin "33") (pinfunction "RX_CTL/CLK125_EN_33") (pintype "bidirectional"))
    )
    (net (code "31") (name "/TXRXA_N") (class "Default")
      (node (ref "CON8000") (pin "3") (pintype "passive"))
      (node (ref "U8000") (pin "3") (pinfunction "TXRXM_A_3") (pintype "passive"))
    )
    (net (code "32") (name "/TXRXA_P") (class "Default")
      (node (ref "CON8000") (pin "2") (pintype "passive"))
      (node (ref "U8000") (pin "2") (pinfunction "TXRXP_A_2") (pintype "passive"))
    )
    (net (code "33") (name "/TXRXB_N") (class "Default")
      (node (ref "CON8000") (pin "5") (pintype "passive"))
      (node (ref "U8000") (pin "6") (pinfunction "TXRXM_B_6") (pintype "passive"))
    )
    (net (code "34") (name "/TXRXB_P") (class "Default")
      (node (ref "CON8000") (pin "4") (pintype "passive"))
      (node (ref "U8000") (pin "5") (pinfunction "TXRXP_B_5") (pintype "passive"))
    )
    (net (code "35") (name "/TXRXC_N") (class "Default")
      (node (ref "CON8000") (pin "7") (pintype "passive"))
      (node (ref "U8000") (pin "8") (pinfunction "TXRXM_C_8") (pintype "passive"))
    )
    (net (code "36") (name "/TXRXC_P") (class "Default")
      (node (ref "CON8000") (pin "6") (pintype "passive"))
      (node (ref "U8000") (pin "7") (pinfunction "TXRXP_C_7") (pintype "passive"))
    )
    (net (code "37") (name "/TXRXD_N") (class "Default")
      (node (ref "CON8000") (pin "9") (pintype "passive"))
      (node (ref "U8000") (pin "11") (pinfunction "TXRXM_D_11") (pintype "passive"))
    )
    (net (code "38") (name "/TXRXD_P") (class "Default")
      (node (ref "CON8000") (pin "8") (pintype "passive"))
      (node (ref "U8000") (pin "10") (pinfunction "TXRXP_D_10") (pintype "passive"))
    )
    (net (code "39") (name "GND") (class "Default")
      (node (ref "C8000") (pin "2") (pinfunction "2_2") (pintype "passive"))
      (node (ref "C8001") (pin "2") (pinfunction "2_2") (pintype "passive"))
      (node (ref "C8002") (pin "2") (pinfunction "2_2") (pintype "passive"))
      (node (ref "C8003") (pin "2") (pinfunction "2_2") (pintype "passive"))
      (node (ref "C8004") (pin "2") (pinfunction "2_2") (pintype "passive"))
      (node (ref "C8005") (pin "2") (pinfunction "2_2") (pintype "passive"))
      (node (ref "C8006") (pin "2") (pinfunction "2_2") (pintype "passive"))
      (node (ref "C8007") (pin "2") (pinfunction "2_2") (pintype "passive"))
      (node (ref "C8008") (pin "2") (pinfunction "2_2") (pintype "passive"))
      (node (ref "C8009") (pin "2") (pinfunction "2_2") (pintype "passive"))
      (node (ref "C8010") (pin "2") (pinfunction "2_2") (pintype "passive"))
      (node (ref "C8011") (pin "2") (pinfunction "2_2") (pintype "passive"))
      (node (ref "C8012") (pin "2") (pinfunction "2_2") (pintype "passive"))
      (node (ref "C8013") (pin "2") (pinfunction "2_2") (pintype "passive"))
      (node (ref "C8014") (pin "2") (pinfunction "2_2") (pintype "passive"))
      (node (ref "C8015") (pin "2") (pinfunction "2_2") (pintype "passive"))
      (node (ref "C8016") (pin "2") (pinfunction "2_2") (pintype "passive"))
      (node (ref "C8017") (pin "2") (pinfunction "2_2") (pintype "passive"))
      (node (ref "C8018") (pin "2") (pinfunction "2_2") (pintype "passive"))
      (node (ref "C8019") (pin "2") (pinfunction "2_2") (pintype "passive"))
      (node (ref "C8020") (pin "2") (pinfunction "2_2") (pintype "passive"))
      (node (ref "C8021") (pin "2") (pinfunction "2_2") (pintype "passive"))
      (node (ref "C8022") (pin "2") (pinfunction "2_2") (pintype "passive"))
      (node (ref "C8023") (pin "2") (pinfunction "2_2") (pintype "passive"))
      (node (ref "C8024") (pin "2") (pinfunction "2_2") (pintype "passive"))
      (node (ref "C8025") (pin "2") (pinfunction "2_2") (pintype "passive"))
      (node (ref "C8026") (pin "2") (pinfunction "2_2") (pintype "passive"))
      (node (ref "C8027") (pin "2") (pinfunction "2_2") (pintype "passive"))
      (node (ref "CON8000") (pin "1") (pintype "passive"))
      (node (ref "R8012") (pin "1") (pinfunction "1_1") (pintype "passive"))
      (node (ref "R8028") (pin "1") (pinfunction "1_1") (pintype "passive"))
      (node (ref "R8029") (pin "1") (pinfunction "1_1") (pintype "passive"))
      (node (ref "R8030") (pin "1") (pinfunction "1_1") (pintype "passive"))
      (node (ref "R8031") (pin "1") (pinfunction "1_1") (pintype "passive"))
      (node (ref "R8032") (pin "1") (pinfunction "1_1") (pintype "passive"))
      (node (ref "R8033") (pin "1") (pinfunction "1_1") (pintype "passive"))
      (node (ref "R8034") (pin "1") (pinfunction "1_1") (pintype "passive"))
      (node (ref "R8035") (pin "1") (pinfunction "1_1") (pintype "passive"))
      (node (ref "R8037") (pin "1") (pinfunction "1_1") (pintype "passive"))
      (node (ref "U8000") (pin "29") (pinfunction "VSS_29") (pintype "power_in"))
      (node (ref "U8000") (pin "49") (pinfunction "P_VSS_49") (pintype "power_in"))
      (node (ref "U8001") (pin "1") (pinfunction "GND_1") (pintype "power_in"))
      (node (ref "U8002") (pin "3") (pinfunction "GND_3") (pintype "passive"))
      (node (ref "Y8000") (pin "2") (pinfunction "GND_2") (pintype "passive"))
      (node (ref "Y8000") (pin "4") (pinfunction "GND_4") (pintype "passive"))
    )
    (net (code "40") (name "Net-(C8000-Pad1)") (class "Default")
      (node (ref "C8000") (pin "1") (pinfunction "1_1") (pintype "passive"))
      (node (ref "C8001") (pin "1") (pinfunction "1_1") (pintype "passive"))
      (node (ref "C8002") (pin "1") (pinfunction "1_1") (pintype "passive"))
      (node (ref "C8003") (pin "1") (pinfunction "1_1") (pintype "passive"))
      (node (ref "FB8002") (pin "1") (pinfunction "1_1") (pintype "passive"))
      (node (ref "U8000") (pin "16") (pinfunction "DVDDH_16") (pintype "power_in"))
      (node (ref "U8000") (pin "34") (pinfunction "DVDDH_34") (pintype "power_in"))
      (node (ref "U8000") (pin "40") (pinfunction "DVDDH_40") (pintype "power_in"))
    )
    (net (code "41") (name "Net-(C8004-Pad1)") (class "Default")
      (node (ref "C8004") (pin "1") (pinfunction "1_1") (pintype "passive"))
      (node (ref "C8005") (pin "1") (pinfunction "1_1") (pintype "passive"))
      (node (ref "C8006") (pin "1") (pinfunction "1_1") (pintype "passive"))
      (node (ref "FB8000") (pin "1") (pinfunction "1_1") (pintype "passive"))
      (node (ref "U8000") (pin "1") (pinfunction "AVDDH_1") (pintype "power_in"))
      (node (ref "U8000") (pin "12") (pinfunction "AVDDH_12") (pintype "power_in"))
    )
    (net (code "42") (name "Net-(C8007-Pad1)") (class "Default")
      (node (ref "C8007") (pin "1") (pinfunction "1_1") (pintype "passive"))
      (node (ref "C8008") (pin "1") (pinfunction "1_1") (pintype "passive"))
      (node (ref "C8009") (pin "1") (pinfunction "1_1") (pintype "passive"))
      (node (ref "C8010") (pin "1") (pinfunction "1_1") (pintype "passive"))
      (node (ref "C8011") (pin "1") (pinfunction "1_1") (pintype "passive"))
      (node (ref "C8012") (pin "1") (pinfunction "1_1") (pintype "passive"))
      (node (ref "FB8003") (pin "1") (pinfunction "1_1") (pintype "passive"))
      (node (ref "U8000") (pin "18") (pinfunction "DVDDL_18") (pintype "power_in"))
      (node (ref "U8000") (pin "23") (pinfunction "DVDDL_23") (pintype "power_in"))
      (node (ref "U8000") (pin "26") (pinfunction "DVDDL_26") (pintype "power_in"))
      (node (ref "U8000") (pin "30") (pinfunction "DVDDL_30") (pintype "power_in"))
      (node (ref "U8000") (pin "39") (pinfunction "DVDDL_39") (pintype "power_in"))
    )
    (net (code "43") (name "Net-(CON8000-Pad12)") (class "Default")
      (node (ref "CON8000") (pin "12") (pintype "passive"))
      (node (ref "R8016") (pin "1") (pinfunction "1_1") (pintype "passive"))
    )
    (net (code "44") (name "Net-(CON8000-Pad14)") (class "Default")
      (node (ref "CON8000") (pin "14") (pintype "passive"))
      (node (ref "R8017") (pin "1") (pinfunction "1_1") (pintype "passive"))
    )
    (net (code "45") (name "Net-(U8000-AVDDL_PLL)") (class "Default")
      (node (ref "C8013") (pin "1") (pinfunction "1_1") (pintype "passive"))
      (node (ref "C8014") (pin "1") (pinfunction "1_1") (pintype "passive"))
      (node (ref "C8015") (pin "1") (pinfunction "1_1") (pintype "passive"))
      (node (ref "C8016") (pin "1") (pinfunction "1_1") (pintype "passive"))
      (node (ref "C8017") (pin "1") (pinfunction "1_1") (pintype "passive"))
      (node (ref "FB8001") (pin "1") (pinfunction "1_1") (pintype "passive"))
      (node (ref "U8000") (pin "4") (pinfunction "AVDDL_4") (pintype "power_in"))
      (node (ref "U8000") (pin "44") (pinfunction "AVDDL_PLL_44") (pintype "power_in"))
      (node (ref "U8000") (pin "9") (pinfunction "AVDDL_9") (pintype "power_in"))
    )
    (net (code "46") (name "Net-(U8000-ISET)") (class "Default")
      (node (ref "R8012") (pin "2") (pinfunction "2_2") (pintype "passive"))
      (node (ref "U8000") (pin "48") (pinfunction "ISET_48") (pintype "input"))
    )
    (net (code "47") (name "Net-(U8000-LDO_O)") (class "Default")
      (node (ref "TP8000") (pin "1") (pinfunction "1_1") (pintype "passive"))
      (node (ref "U8000") (pin "43") (pinfunction "LDO_O_43") (pintype "output"))
    )
    (net (code "48") (name "Net-(U8000-MDC)") (class "Default")
      (node (ref "R8014") (pin "2") (pinfunction "2_2") (pintype "passive"))
      (node (ref "U8000") (pin "36") (pinfunction "MDC_36") (pintype "input"))
    )
    (net (code "49") (name "Net-(U8000-MDIO)") (class "Default")
      (node (ref "R8015") (pin "2") (pinfunction "2_2") (pintype "passive"))
      (node (ref "U8000") (pin "37") (pinfunction "MDIO_37") (pintype "bidirectional"))
    )
    (net (code "50") (name "Net-(U8000-TXC)") (class "Default")
      (node (ref "R8000") (pin "2") (pinfunction "2_2") (pintype "passive"))
      (node (ref "U8000") (pin "24") (pinfunction "TXC_24") (pintype "input"))
    )
    (net (code "51") (name "Net-(U8000-TXD0)") (class "Default")
      (node (ref "R8002") (pin "2") (pinfunction "2_2") (pintype "passive"))
      (node (ref "U8000") (pin "19") (pinfunction "TXD0_19") (pintype "input"))
    )
    (net (code "52") (name "Net-(U8000-TXD1)") (class "Default")
      (node (ref "R8003") (pin "2") (pinfunction "2_2") (pintype "passive"))
      (node (ref "U8000") (pin "20") (pinfunction "TXD1_20") (pintype "input"))
    )
    (net (code "53") (name "Net-(U8000-TXD2)") (class "Default")
      (node (ref "R8004") (pin "2") (pinfunction "2_2") (pintype "passive"))
      (node (ref "U8000") (pin "21") (pinfunction "TXD2_21") (pintype "input"))
    )
    (net (code "54") (name "Net-(U8000-TXD3)") (class "Default")
      (node (ref "R8005") (pin "2") (pinfunction "2_2") (pintype "passive"))
      (node (ref "U8000") (pin "22") (pinfunction "TXD3_22") (pintype "input"))
    )
    (net (code "55") (name "Net-(U8000-TX_CTL)") (class "Default")
      (node (ref "R8001") (pin "2") (pinfunction "2_2") (pintype "passive"))
      (node (ref "U8000") (pin "25") (pinfunction "TX_CTL_25") (pintype "input"))
    )
    (net (code "56") (name "Net-(U8000-XI)") (class "Default")
      (node (ref "C8020") (pin "1") (pinfunction "1_1") (pintype "passive"))
      (node (ref "U8000") (pin "46") (pinfunction "XI_46") (pintype "input"))
      (node (ref "Y8000") (pin "3") (pinfunction "OSC2_3") (pintype "passive"))
    )
    (net (code "57") (name "Net-(U8000-XO)") (class "Default")
      (node (ref "C8019") (pin "1") (pinfunction "1_1") (pintype "passive"))
      (node (ref "U8000") (pin "45") (pinfunction "XO_45") (pintype "output"))
      (node (ref "Y8000") (pin "1") (pinfunction "OSC1_1") (pintype "passive"))
    )
    (net (code "58") (name "Net-(U8001-EN)") (class "Default")
      (node (ref "R8041") (pin "1") (pinfunction "1_1") (pintype "passive"))
      (node (ref "U8001") (pin "8") (pinfunction "EN_8") (pintype "input"))
    )
    (net (code "59") (name "SHIELD_ETH") (class "Default")
      (node (ref "C8018") (pin "1") (pinfunction "1_1") (pintype "passive"))
      (node (ref "CON8000") (pin "0") (pintype "passive"))
    )
    (net (code "60") (name "VDD_HV_A") (class "Default")
      (node (ref "C8025") (pin "1") (pinfunction "1_1") (pintype "passive"))
      (node (ref "R8039") (pin "2") (pinfunction "2_2") (pintype "passive"))
      (node (ref "R8040") (pin "2") (pinfunction "2_2") (pintype "passive"))
      (node (ref "R8041") (pin "2") (pinfunction "2_2") (pintype "passive"))
      (node (ref "U8001") (pin "2") (pinfunction "VREF_A_2") (pintype "input"))
    )
    (net (code "61") (name "VDD_HV_B") (class "Default")
      (node (ref "C8026") (pin "1") (pinfunction "1_1") (pintype "passive"))
      (node (ref "C8027") (pin "1") (pinfunction "1_1") (pintype "passive"))
      (node (ref "R8042") (pin "2") (pinfunction "2_2") (pintype "passive"))
      (node (ref "R8043") (pin "2") (pinfunction "2_2") (pintype "passive"))
      (node (ref "R8044") (pin "2") (pinfunction "2_2") (pintype "passive"))
      (node (ref "U8001") (pin "7") (pinfunction "VREF_B_7") (pintype "input"))
      (node (ref "U8002") (pin "5") (pinfunction "VCC_5") (pintype "passive"))
    )
    (net (code "62") (name "VREG_1P2") (class "Default")
      (node (ref "C8023") (pin "1") (pinfunction "1_1") (pintype "passive"))
      (node (ref "C8024") (pin "1") (pinfunction "1_1") (pintype "passive"))
      (node (ref "FB8001") (pin "2") (pinfunction "2_2") (pintype "passive"))
      (node (ref "FB8003") (pin "2") (pinfunction "2_2") (pintype "passive"))
    )
    (net (code "63") (name "VREG_3P3") (class "Default")
      (node (ref "C8021") (pin "1") (pinfunction "1_1") (pintype "passive"))
      (node (ref "C8022") (pin "1") (pinfunction "1_1") (pintype "passive"))
      (node (ref "CON8000") (pin "11") (pintype "passive"))
      (node (ref "CON8000") (pin "13") (pintype "passive"))
      (node (ref "FB8000") (pin "2") (pinfunction "2_2") (pintype "passive"))
      (node (ref "FB8002") (pin "2") (pinfunction "2_2") (pintype "passive"))
      (node (ref "R8018") (pin "2") (pinfunction "2_2") (pintype "passive"))
      (node (ref "R8019") (pin "2") (pinfunction "2_2") (pintype "passive"))
      (node (ref "R8020") (pin "2") (pinfunction "2_2") (pintype "passive"))
      (node (ref "R8021") (pin "2") (pinfunction "2_2") (pintype "passive"))
      (node (ref "R8022") (pin "2") (pinfunction "2_2") (pintype "passive"))
      (node (ref "R8023") (pin "2") (pinfunction "2_2") (pintype "passive"))
      (node (ref "R8024") (pin "2") (pinfunction "2_2") (pintype "passive"))
      (node (ref "R8025") (pin "2") (pinfunction "2_2") (pintype "passive"))
      (node (ref "R8026") (pin "2") (pinfunction "2_2") (pintype "passive"))
      (node (ref "R8027") (pin "2") (pinfunction "2_2") (pintype "passive"))
      (node (ref "R8036") (pin "2") (pinfunction "2_2") (pintype "passive"))
      (node (ref "R8038") (pin "2") (pinfunction "2_2") (pintype "passive"))
    )
    (net (code "64") (name "unconnected-(CON8000-NC-Pad10)") (class "Default")
      (node (ref "CON8000") (pin "10") (pinfunction "NC_10") (pintype "passive"))
    )
    (net (code "65") (name "unconnected-(U8000-NC-Pad13)") (class "Default")
      (node (ref "U8000") (pin "13") (pinfunction "NC_13") (pintype "passive"))
    )
    (net (code "66") (name "unconnected-(U8000-NC-Pad14)") (class "Default")
      (node (ref "U8000") (pin "14") (pinfunction "NC_14") (pintype "passive"))
    )
    (net (code "67") (name "unconnected-(U8000-NC-Pad47)") (class "Default")
      (node (ref "U8000") (pin "47") (pinfunction "NC_47") (pintype "passive"))
    )
  )
)
